# SENSOR.net
KiCad netlist of a schematic drawn in Altium Designer
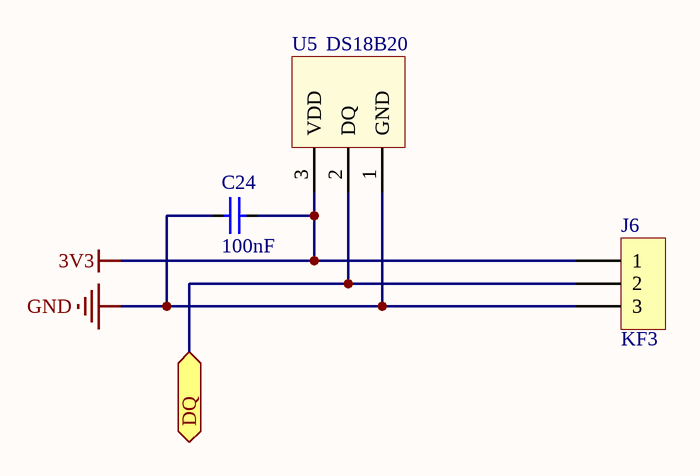
[diagram p0: SENSOR.SchDoc]

(export (version "E")
  (design (tool "Eeschema 10.0.6"))
  (components
    (comp (ref "C24")
      (value "100nF")
      (footprint "CAP_0805")
      (description "Capacitor")
      (fields (field (name "PUBLISHER") "Altium Limited"))
      (libsource (lib "My Library") (part "CapSMD"))
    )
    (comp (ref "J6")
      (value "KF3")
      (footprint "KF3-5.08")
      (fields
        (field (name "MANUFACTURER") "Würth Elektronik eiSos GmbH")
        (field (name "PARTNO") "691103110003")
        (field (name "CREATED BY") "Karrer Zheng")
      )
      (libsource (lib "My Library") (part "KF3"))
    )
    (comp (ref "U5")
      (value "DS18B20")
      (footprint "QTO-92A")
      (description "High Precision  1-Wire® Digital Thermometer")
      (libsource (lib "My Library") (part "DS18B20"))
    )
  )
  (nets
    (net (code "1") (name "/DQ") (class "Default")
      (node (ref "J6") (pin "2") (pinfunction "2_2") (pintype "passive"))
      (node (ref "U5") (pin "2") (pinfunction "DQ_2") (pintype "passive"))
    )
    (net (code "2") (name "3V3") (class "Default")
      (node (ref "C24") (pin "1") (pinfunction "1_1") (pintype "passive"))
      (node (ref "J6") (pin "1") (pinfunction "1_1") (pintype "passive"))
      (node (ref "U5") (pin "3") (pinfunction "VDD_3") (pintype "passive"))
    )
    (net (code "3") (name "GND") (class "Default")
      (node (ref "C24") (pin "2") (pinfunction "2_2") (pintype "passive"))
      (node (ref "J6") (pin "3") (pinfunction "3_3") (pintype "passive"))
      (node (ref "U5") (pin "1") (pinfunction "GND_1") (pintype "passive"))
    )
  )
)
